# ADC-EXTERNAL_CLOCK_INPUT.net
KiCad netlist of a schematic drawn in Altium Designer
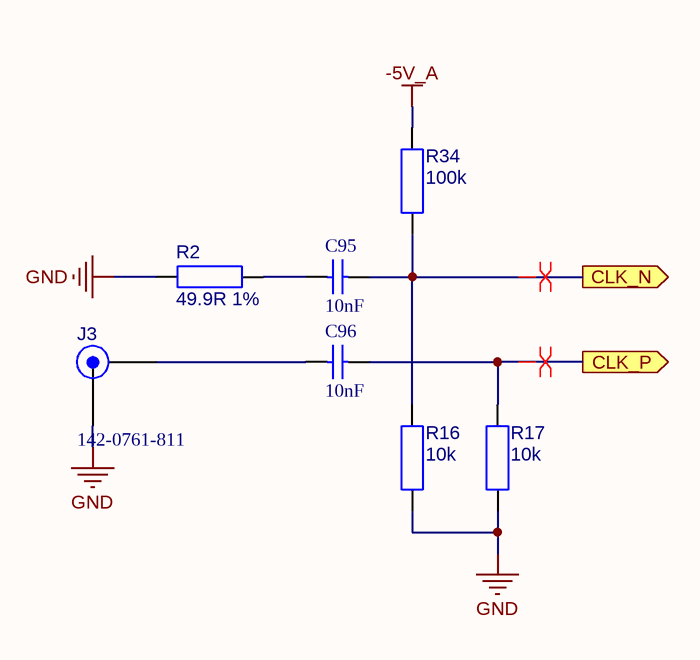
[diagram p0: ADC-EXTERNAL CLOCK INPUT.SchDoc]

(export (version "E")
  (design (tool "Eeschema 10.0.6"))
  (components
    (comp (ref "C95")
      (value "10nF")
      (footprint "CAPC1005X55N")
      (description "Capacitor 0402 SMD")
      (fields (field (name "CREATED_BY") "EDA-ASA") (field (name "CHECKED_BY") "*"))
      (libsource (lib "EDA-Passive") (part "cap0402"))
    )
    (comp (ref "C96")
      (value "10nF")
      (footprint "CAPC1005X55N")
      (description "Capacitor 0402 SMD")
      (fields (field (name "CREATED_BY") "EDA-ASA") (field (name "CHECKED_BY") "*"))
      (libsource (lib "EDA-Passive") (part "cap0402"))
    )
    (comp (ref "J3")
      (value "142-0761-811")
      (footprint "EDGE_LAUNCH_TH_SMA")
      (description "High Frequency SMA End Lauch Connector")
      (fields
        (field (name "MANUFACTURER") "JOHNSON")
        (field (name "MANUFACTURER_PN") "142-0761-811")
        (field (name "CREATED_BY") "CT")
        (field (name "CHECKED_BY") "*")
      )
      (libsource (lib "Charles-TEMP") (part "142-0761-811"))
    )
    (comp (ref "R2")
      (value "49.9R 1%")
      (footprint "0603")
      (description "RESISTOR SMD 0603")
      (fields (field (name "CREATED_BY") "*") (field (name "CHECKED_BY") "NN"))
      (libsource (lib "EDA_Passive") (part "RES-0805"))
    )
    (comp (ref "R16")
      (value "10k")
      (footprint "0603")
      (description "RESISTOR SMD 0603")
      (fields (field (name "CREATED_BY") "*") (field (name "CHECKED_BY") "NN"))
      (libsource (lib "EDA_Passive") (part "RES-0805"))
    )
    (comp (ref "R17")
      (value "10k")
      (footprint "0603")
      (description "RESISTOR SMD 0603")
      (fields (field (name "CREATED_BY") "*") (field (name "CHECKED_BY") "NN"))
      (libsource (lib "EDA_Passive") (part "RES-0805"))
    )
    (comp (ref "R34")
      (value "100k")
      (footprint "0603")
      (description "RESISTOR SMD 0603")
      (fields (field (name "CREATED_BY") "*") (field (name "CHECKED_BY") "NN"))
      (libsource (lib "EDA_Passive") (part "RES-0805"))
    )
  )
  (nets
    (net (code "1") (name "-5V_A") (class "Default")
      (node (ref "R34") (pin "2") (pinfunction "2_2") (pintype "passive"))
    )
    (net (code "2") (name "/CLK_N") (class "Default")
      (node (ref "C95") (pin "2") (pinfunction "2_2") (pintype "passive"))
      (node (ref "R16") (pin "2") (pinfunction "2_2") (pintype "passive"))
      (node (ref "R34") (pin "1") (pinfunction "1_1") (pintype "passive"))
    )
    (net (code "3") (name "/CLK_P") (class "Default")
      (node (ref "C96") (pin "2") (pinfunction "2_2") (pintype "passive"))
      (node (ref "R17") (pin "2") (pinfunction "2_2") (pintype "passive"))
    )
    (net (code "4") (name "GND") (class "Default")
      (node (ref "J3") (pin "2") (pinfunction "2_2") (pintype "passive"))
      (node (ref "R16") (pin "1") (pinfunction "1_1") (pintype "passive"))
      (node (ref "R17") (pin "1") (pinfunction "1_1") (pintype "passive"))
      (node (ref "R2") (pin "1") (pinfunction "1_1") (pintype "passive"))
    )
    (net (code "5") (name "Net-(C95-Pad1)") (class "Default")
      (node (ref "C95") (pin "1") (pinfunction "1_1") (pintype "passive"))
      (node (ref "R2") (pin "2") (pinfunction "2_2") (pintype "passive"))
    )
    (net (code "6") (name "Net-(C96-Pad1)") (class "Default")
      (node (ref "C96") (pin "1") (pinfunction "1_1") (pintype "passive"))
      (node (ref "J3") (pin "1") (pinfunction "1_1") (pintype "passive"))
    )
  )
)
